# drive.net
KiCad netlist of a schematic drawn in Altium Designer
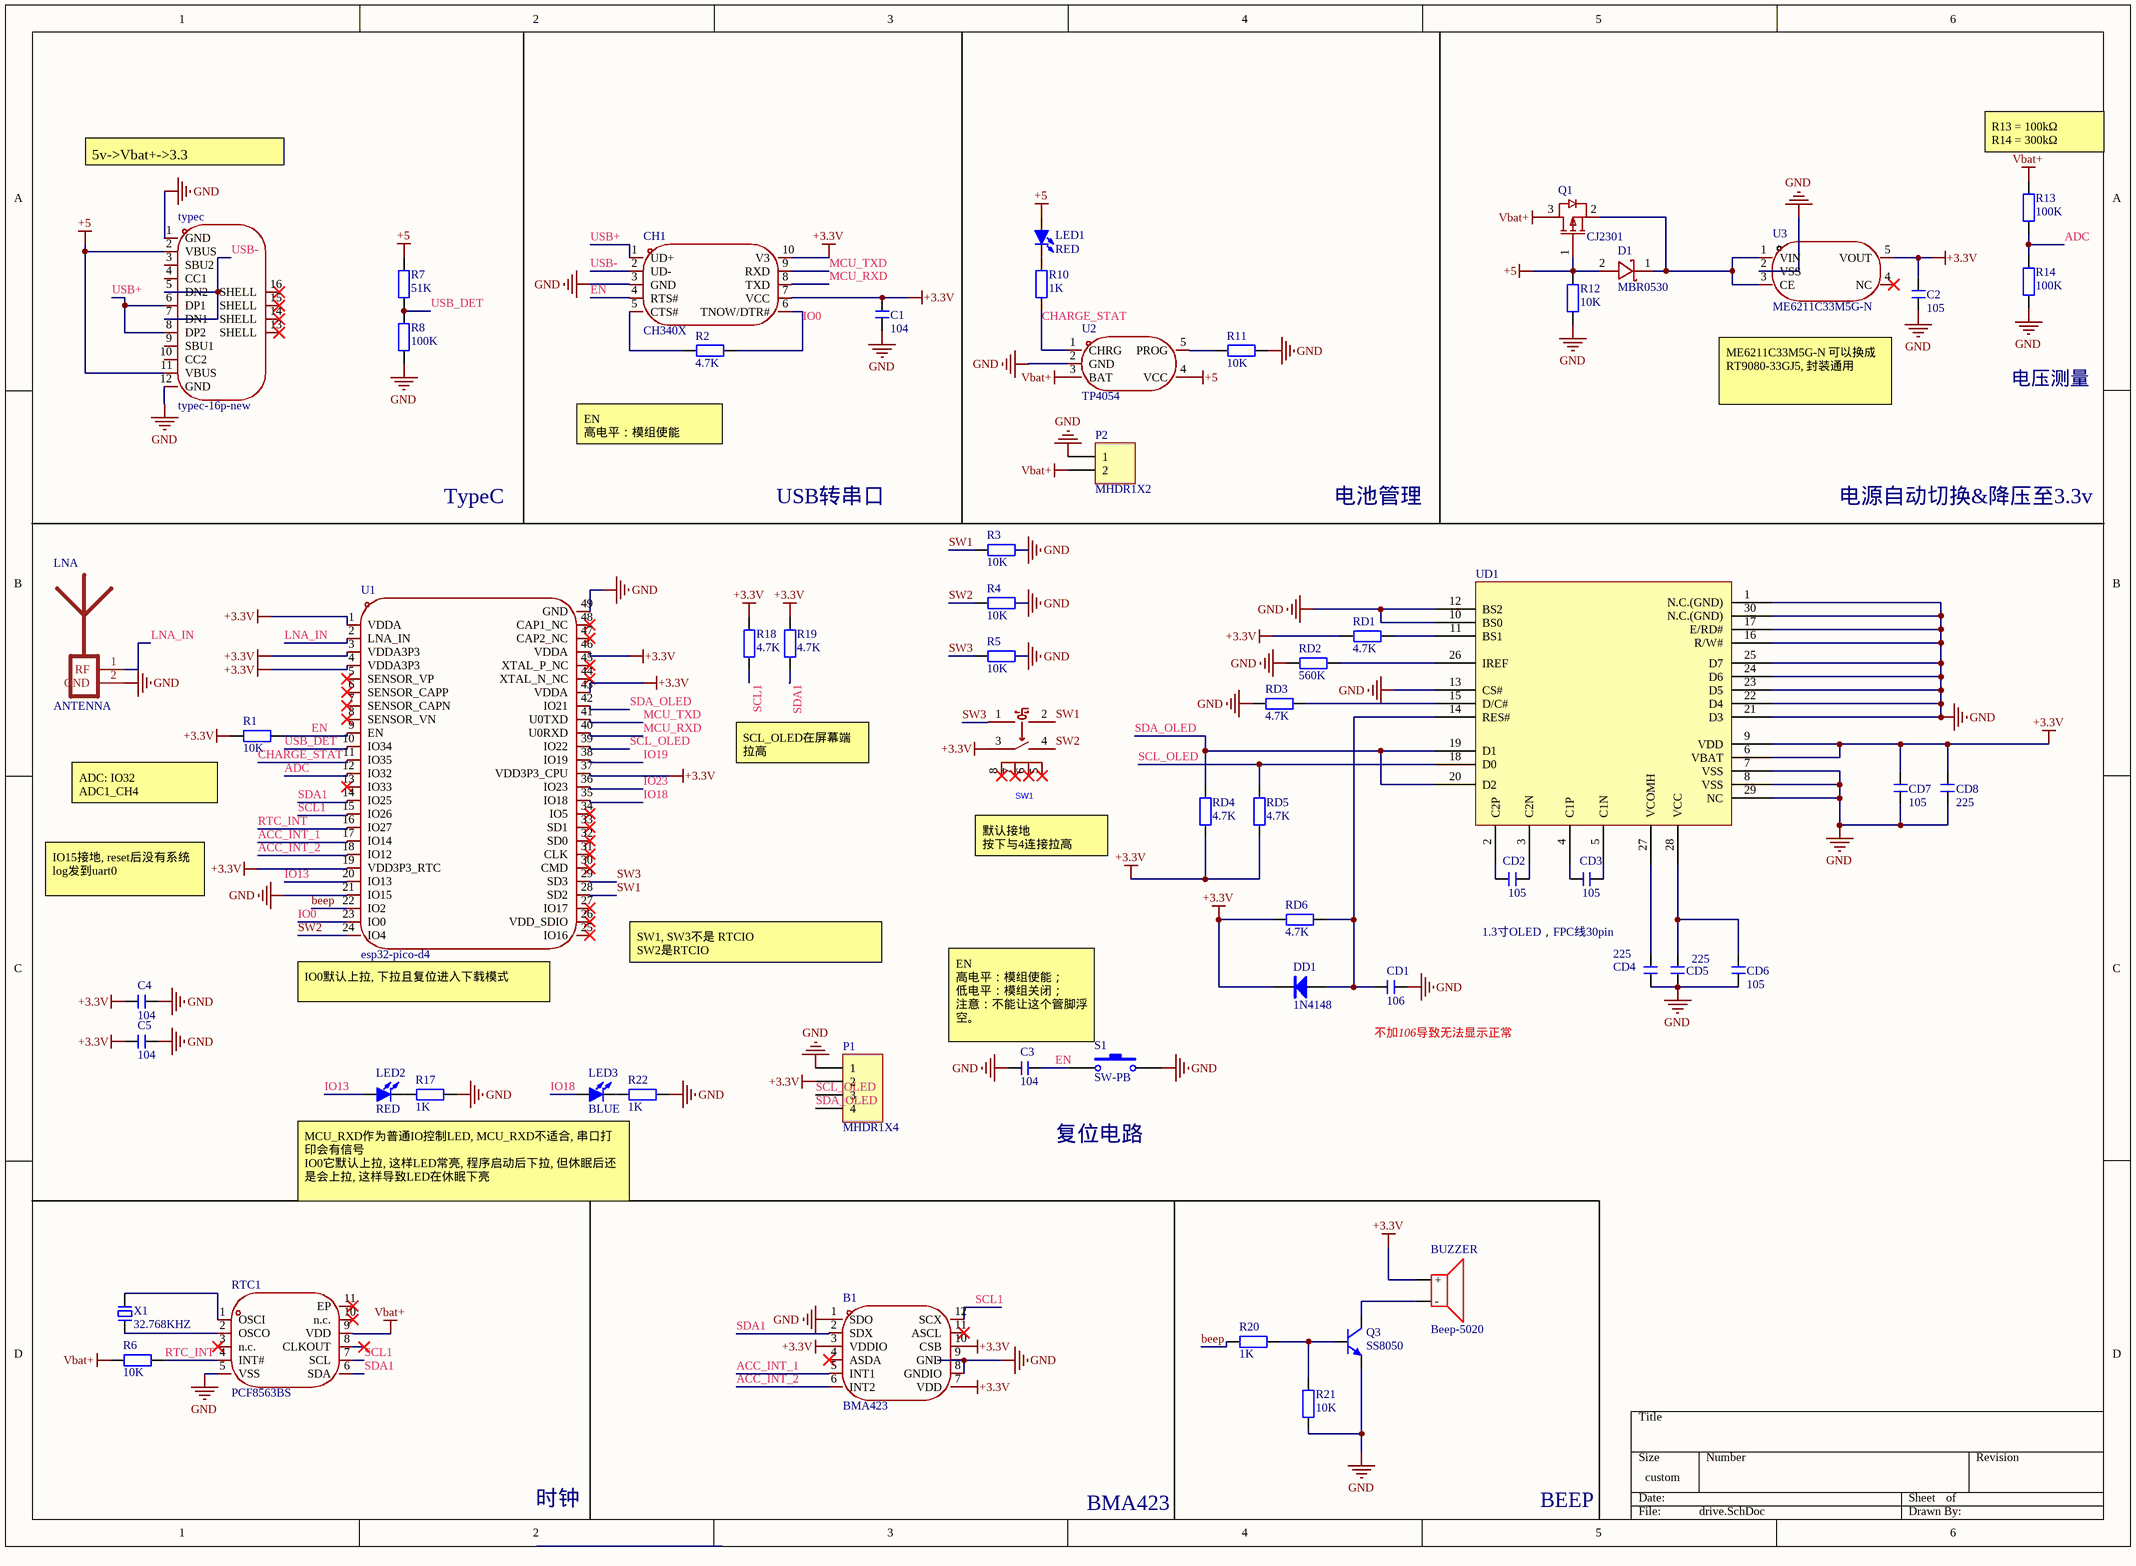
[diagram p0: drive.SchDoc]

(export (version "E")
  (design (tool "Eeschema 10.0.6"))
  (components
    (comp (ref "B1") (value "BMA423") (footprint "LGA-12(2x2)-2") (libsource (lib "Schlib1") (part "BMA423")))
    (comp (ref "BUZZER")
      (value "Beep-5020")
      (footprint "5020BUZZER")
      (description "贴片蜂鸣器5020最小封装")
      (libsource (lib "我的元件") (part "Beep-5020"))
    )
    (comp (ref "C1")
      (value "104")
      (footprint "C0402-min")
      (description "无极性贴片电容")
      (fields (field (name "版权归属") "源创客"))
      (libsource (lib "3.1   - 电阻-电容-电感") (part "C"))
    )
    (comp (ref "C2")
      (value "105")
      (footprint "C0402-min")
      (description "无极性贴片电容")
      (fields (field (name "版权归属") "源创客"))
      (libsource (lib "3.1   - 电阻-电容-电感") (part "C"))
    )
    (comp (ref "C3")
      (value "104")
      (footprint "C0402-min")
      (description "无极性贴片电容")
      (fields (field (name "版权归属") "源创客"))
      (libsource (lib "3.1   - 电阻-电容-电感") (part "C"))
    )
    (comp (ref "C4")
      (value "104")
      (footprint "C0402-min")
      (description "无极性贴片电容")
      (fields (field (name "版权归属") "源创客"))
      (libsource (lib "3.1   - 电阻-电容-电感") (part "C"))
    )
    (comp (ref "C5")
      (value "104")
      (footprint "C0402-min")
      (description "无极性贴片电容")
      (fields (field (name "版权归属") "源创客"))
      (libsource (lib "3.1   - 电阻-电容-电感") (part "C"))
    )
    (comp (ref "CD1")
      (value "106")
      (footprint "C0402-min")
      (description "无极性贴片电容")
      (fields (field (name "版权归属") "源创客"))
      (libsource (lib "3.1   - 电阻-电容-电感") (part "C"))
    )
    (comp (ref "CD2")
      (value "105")
      (footprint "C0402-min")
      (description "无极性贴片电容")
      (fields (field (name "版权归属") "源创客"))
      (libsource (lib "3.1   - 电阻-电容-电感") (part "C"))
    )
    (comp (ref "CD3")
      (value "105")
      (footprint "C0402-min")
      (description "无极性贴片电容")
      (fields (field (name "版权归属") "源创客"))
      (libsource (lib "3.1   - 电阻-电容-电感") (part "C"))
    )
    (comp (ref "CD4")
      (value "225")
      (footprint "C0402-min")
      (description "无极性贴片电容")
      (fields (field (name "版权归属") "源创客"))
      (libsource (lib "3.1   - 电阻-电容-电感") (part "C"))
    )
    (comp (ref "CD5")
      (value "225")
      (footprint "C0402-min")
      (description "无极性贴片电容")
      (fields (field (name "版权归属") "源创客"))
      (libsource (lib "3.1   - 电阻-电容-电感") (part "C"))
    )
    (comp (ref "CD6")
      (value "105")
      (footprint "C0402-min")
      (description "无极性贴片电容")
      (fields (field (name "版权归属") "源创客"))
      (libsource (lib "3.1   - 电阻-电容-电感") (part "C"))
    )
    (comp (ref "CD7")
      (value "105")
      (footprint "C0402-min")
      (description "无极性贴片电容")
      (fields (field (name "版权归属") "源创客"))
      (libsource (lib "3.1   - 电阻-电容-电感") (part "C"))
    )
    (comp (ref "CD8")
      (value "225")
      (footprint "C0402-min")
      (description "无极性贴片电容")
      (fields (field (name "版权归属") "源创客"))
      (libsource (lib "3.1   - 电阻-电容-电感") (part "C"))
    )
    (comp (ref "CH1") (value "CH340X") (footprint "MSOP-10") (libsource (lib "Schlib1") (part "CH340X")))
    (comp (ref "D1") (value "MBR0530") (footprint "SOD-123") (libsource (lib "Schlib1") (part "MBR0530T1G")))
    (comp (ref "DD1")
      (value "1N4148")
      (footprint "SOD-323")
      (description "高速开关二极管")
      (fields (field (name "版权归属") "源创客"))
      (libsource (lib "8.1   - 二极管-整流桥") (part "1N4148"))
    )
    (comp (ref "LED1")
      (value "RED")
      (footprint "LED0402")
      (description "贴片LED")
      (fields (field (name "版权归属") "源创客"))
      (libsource (lib "9.1   - LED") (part "LED-SMD"))
    )
    (comp (ref "LED2")
      (value "RED")
      (footprint "LED0402")
      (description "贴片LED")
      (fields (field (name "版权归属") "源创客"))
      (libsource (lib "9.1   - LED") (part "LED-SMD"))
    )
    (comp (ref "LED3")
      (value "BLUE")
      (footprint "LED0402")
      (description "贴片LED")
      (fields (field (name "版权归属") "源创客"))
      (libsource (lib "9.1   - LED") (part "LED-SMD"))
    )
    (comp (ref "LNA") (value "ANTENNA") (footprint "SWRA117D") (libsource (lib "Schlib1") (part "ANTENNA")))
    (comp (ref "P1")
      (value "MHDR1X4")
      (footprint "MHDR1X4")
      (description "Header, 4-Pin")
      (fields (field (name "PUBLISHER") "Altium Limited"))
      (libsource (lib "Miscellaneous Connectors") (part "MHDR1X4"))
    )
    (comp (ref "P2")
      (value "MHDR1X2")
      (footprint "MHDR1X2")
      (description "Header, 2-Pin")
      (fields (field (name "PUBLISHER") "Altium Limited"))
      (libsource (lib "Miscellaneous Connectors") (part "MHDR1X2"))
    )
    (comp (ref "Q1") (value "CJ2301") (footprint "SOT-23-3") (libsource (lib "Schlib1") (part "CJ2301")))
    (comp (ref "Q3")
      (value "SS8050")
      (footprint "SOT-23-3")
      (description "高频放大-NPN型")
      (fields (field (name "版权归属") "源创客"))
      (libsource (lib "6.2   - 三极管") (part "8050-SMD"))
    )
    (comp (ref "R1")
      (value "10K")
      (footprint "R0402")
      (description "贴片电阻")
      (fields (field (name "版权归属") "源创客"))
      (libsource (lib "3.1   - 电阻-电容-电感") (part "R"))
    )
    (comp (ref "R2")
      (value "4.7K")
      (footprint "R0402")
      (description "贴片电阻")
      (fields (field (name "版权归属") "源创客"))
      (libsource (lib "3.1   - 电阻-电容-电感") (part "R"))
    )
    (comp (ref "R3")
      (value "10K")
      (footprint "R0402")
      (description "贴片电阻")
      (fields (field (name "版权归属") "源创客"))
      (libsource (lib "3.1   - 电阻-电容-电感") (part "R"))
    )
    (comp (ref "R4")
      (value "10K")
      (footprint "R0402")
      (description "贴片电阻")
      (fields (field (name "版权归属") "源创客"))
      (libsource (lib "3.1   - 电阻-电容-电感") (part "R"))
    )
    (comp (ref "R5")
      (value "10K")
      (footprint "R0402")
      (description "贴片电阻")
      (fields (field (name "版权归属") "源创客"))
      (libsource (lib "3.1   - 电阻-电容-电感") (part "R"))
    )
    (comp (ref "R6")
      (value "10K")
      (footprint "R0402")
      (description "贴片电阻")
      (fields (field (name "版权归属") "源创客"))
      (libsource (lib "3.1   - 电阻-电容-电感") (part "R"))
    )
    (comp (ref "R7")
      (value "51K")
      (footprint "R0402")
      (description "贴片电阻")
      (fields (field (name "版权归属") "源创客"))
      (libsource (lib "3.1   - 电阻-电容-电感") (part "R"))
    )
    (comp (ref "R8")
      (value "100K")
      (footprint "R0402")
      (description "贴片电阻")
      (fields (field (name "版权归属") "源创客"))
      (libsource (lib "3.1   - 电阻-电容-电感") (part "R"))
    )
    (comp (ref "R10")
      (value "1K")
      (footprint "R0402")
      (description "贴片电阻")
      (fields (field (name "版权归属") "源创客"))
      (libsource (lib "3.1   - 电阻-电容-电感") (part "R"))
    )
    (comp (ref "R11")
      (value "10K")
      (footprint "R0402")
      (description "贴片电阻")
      (fields (field (name "版权归属") "源创客"))
      (libsource (lib "3.1   - 电阻-电容-电感") (part "R"))
    )
    (comp (ref "R12")
      (value "10K")
      (footprint "R0402")
      (description "贴片电阻")
      (fields (field (name "版权归属") "源创客"))
      (libsource (lib "3.1   - 电阻-电容-电感") (part "R"))
    )
    (comp (ref "R13")
      (value "100K")
      (footprint "R0402")
      (description "贴片电阻")
      (fields (field (name "版权归属") "源创客"))
      (libsource (lib "3.1   - 电阻-电容-电感") (part "R"))
    )
    (comp (ref "R14")
      (value "100K")
      (footprint "R0402")
      (description "贴片电阻")
      (fields (field (name "版权归属") "源创客"))
      (libsource (lib "3.1   - 电阻-电容-电感") (part "R"))
    )
    (comp (ref "R17")
      (value "1K")
      (footprint "R0402")
      (description "贴片电阻")
      (fields (field (name "版权归属") "源创客"))
      (libsource (lib "3.1   - 电阻-电容-电感") (part "R"))
    )
    (comp (ref "R18")
      (value "4.7K")
      (footprint "R0402")
      (description "贴片电阻")
      (fields (field (name "版权归属") "源创客"))
      (libsource (lib "3.1   - 电阻-电容-电感") (part "R"))
    )
    (comp (ref "R19")
      (value "4.7K")
      (footprint "R0402")
      (description "贴片电阻")
      (fields (field (name "版权归属") "源创客"))
      (libsource (lib "3.1   - 电阻-电容-电感") (part "R"))
    )
    (comp (ref "R20")
      (value "1K")
      (footprint "R0402")
      (description "贴片电阻")
      (fields (field (name "版权归属") "源创客"))
      (libsource (lib "3.1   - 电阻-电容-电感") (part "R"))
    )
    (comp (ref "R21")
      (value "10K")
      (footprint "R0402")
      (description "贴片电阻")
      (fields (field (name "版权归属") "源创客"))
      (libsource (lib "3.1   - 电阻-电容-电感") (part "R"))
    )
    (comp (ref "R22")
      (value "1K")
      (footprint "R0402")
      (description "贴片电阻")
      (fields (field (name "版权归属") "源创客"))
      (libsource (lib "3.1   - 电阻-电容-电感") (part "R"))
    )
    (comp (ref "RD1")
      (value "4.7K")
      (footprint "R0402")
      (description "贴片电阻")
      (fields (field (name "版权归属") "源创客"))
      (libsource (lib "3.1   - 电阻-电容-电感") (part "R"))
    )
    (comp (ref "RD2")
      (value "560K")
      (footprint "R0402")
      (description "贴片电阻")
      (fields (field (name "版权归属") "源创客"))
      (libsource (lib "3.1   - 电阻-电容-电感") (part "R"))
    )
    (comp (ref "RD3")
      (value "4.7K")
      (footprint "R0402")
      (description "贴片电阻")
      (fields (field (name "版权归属") "源创客"))
      (libsource (lib "3.1   - 电阻-电容-电感") (part "R"))
    )
    (comp (ref "RD4")
      (value "4.7K")
      (footprint "R0402")
      (description "贴片电阻")
      (fields (field (name "版权归属") "源创客"))
      (libsource (lib "3.1   - 电阻-电容-电感") (part "R"))
    )
    (comp (ref "RD5")
      (value "4.7K")
      (footprint "R0402")
      (description "贴片电阻")
      (fields (field (name "版权归属") "源创客"))
      (libsource (lib "3.1   - 电阻-电容-电感") (part "R"))
    )
    (comp (ref "RD6")
      (value "4.7K")
      (footprint "R0402")
      (description "贴片电阻")
      (fields (field (name "版权归属") "源创客"))
      (libsource (lib "3.1   - 电阻-电容-电感") (part "R"))
    )
    (comp (ref "RTC1")
      (value "PCF8563BS")
      (footprint "HVSON-10-EP(3x3)")
      (libsource (lib "Schlib1") (part "PCF8563BS"))
    )
    (comp (ref "S1")
      (value "SW-PB")
      (footprint "switch-2x3")
      (description "Switch")
      (fields (field (name "PUBLISHER") "Altium Limited"))
      (libsource (lib "Miscellaneous Devices") (part "SW-PB"))
    )
    (comp (ref "SW1")
      (value "TM-2024A")
      (footprint "LUNBO-min-out")
      (fields (field (name "MANUFACTURER") "XKB Connection(中国星坤)"))
      (libsource (lib "drive") (part "lunbo-min"))
    )
    (comp (ref "typec")
      (value "typec-16p-new")
      (footprint "type-c-16p-new")
      (libsource (lib "Schlib1") (part "typec-16p-new"))
    )
    (comp (ref "U1")
      (value "esp32-pico-d4")
      (footprint "QFN-48-EP(7x7)")
      (libsource (lib "Schlib1") (part "esp32-pico-d4"))
    )
    (comp (ref "U2") (value "TP4054") (footprint "SOT-23-5") (libsource (lib "Schlib1") (part "TP4054")))
    (comp (ref "U3")
      (value "ME6211C33M5G-N")
      (footprint "SOT-23-5")
      (libsource (lib "Schlib1") (part "ME6211C33M5G-N"))
    )
    (comp (ref "UD1")
      (value "1.3寸OLED，FPC线30pin")
      (footprint "0.96OLED")
      (libsource (lib "我的元件") (part "1.3寸OLED，FPC线30pin"))
    )
    (comp (ref "X1")
      (value "32.768KHZ")
      (footprint "SMD3215-2P")
      (description "2脚无源脚晶振")
      (fields (field (name "版权归属") "源创客"))
      (libsource (lib "10.1 - 保险丝-晶振") (part "XTAL-2P"))
    )
  )
  (nets
    (net (code "1") (name "+3.3V") (class "Default")
      (node (ref "B1") (pin "10") (pinfunction "CSB_10") (pintype "passive"))
      (node (ref "B1") (pin "3") (pinfunction "VDDIO_3") (pintype "passive"))
      (node (ref "B1") (pin "7") (pinfunction "VDD_7") (pintype "passive"))
      (node (ref "BUZZER") (pin "1") (pinfunction "+_1") (pintype "passive"))
      (node (ref "C1") (pin "2") (pinfunction "2_2") (pintype "passive"))
      (node (ref "C2") (pin "2") (pinfunction "2_2") (pintype "passive"))
      (node (ref "C4") (pin "2") (pinfunction "2_2") (pintype "passive"))
      (node (ref "C5") (pin "2") (pinfunction "2_2") (pintype "passive"))
      (node (ref "CD7") (pin "2") (pinfunction "2_2") (pintype "passive"))
      (node (ref "CD8") (pin "2") (pinfunction "2_2") (pintype "passive"))
      (node (ref "CH1") (pin "10") (pinfunction "V3_10") (pintype "passive"))
      (node (ref "CH1") (pin "7") (pinfunction "VCC_7") (pintype "passive"))
      (node (ref "DD1") (pin "2") (pinfunction "K_2") (pintype "passive"))
      (node (ref "P1") (pin "2") (pinfunction "2_2") (pintype "passive"))
      (node (ref "R1") (pin "1") (pinfunction "1_1") (pintype "passive"))
      (node (ref "R18") (pin "2") (pinfunction "2_2") (pintype "passive"))
      (node (ref "R19") (pin "2") (pinfunction "2_2") (pintype "passive"))
      (node (ref "RD1") (pin "1") (pinfunction "1_1") (pintype "passive"))
      (node (ref "RD4") (pin "1") (pinfunction "1_1") (pintype "passive"))
      (node (ref "RD5") (pin "1") (pinfunction "1_1") (pintype "passive"))
      (node (ref "RD6") (pin "1") (pinfunction "1_1") (pintype "passive"))
      (node (ref "SW1") (pin "3") (pinfunction "3_3") (pintype "passive"))
      (node (ref "U1") (pin "1") (pinfunction "VDDA_1") (pintype "passive"))
      (node (ref "U1") (pin "19") (pinfunction "VDD3P3_RTC_19") (pintype "passive"))
      (node (ref "U1") (pin "3") (pinfunction "VDDA3P3_3") (pintype "passive"))
      (node (ref "U1") (pin "37") (pinfunction "VDD3P3_CPU_37") (pintype "passive"))
      (node (ref "U1") (pin "4") (pinfunction "VDDA3P3_4") (pintype "passive"))
      (node (ref "U1") (pin "43") (pinfunction "VDDA_43") (pintype "passive"))
      (node (ref "U1") (pin "46") (pinfunction "VDDA_46") (pintype "passive"))
      (node (ref "U3") (pin "5") (pinfunction "VOUT_5") (pintype "passive"))
      (node (ref "UD1") (pin "6") (pinfunction "VBAT_6") (pintype "passive"))
      (node (ref "UD1") (pin "9") (pinfunction "VDD_9") (pintype "passive"))
    )
    (net (code "2") (name "+5") (class "Default")
      (node (ref "D1") (pin "2") (pinfunction "A_2") (pintype "passive"))
      (node (ref "LED1") (pin "1") (pinfunction "A_1") (pintype "passive"))
      (node (ref "Q1") (pin "1") (pinfunction "G_1") (pintype "passive"))
      (node (ref "R12") (pin "2") (pinfunction "2_2") (pintype "passive"))
      (node (ref "R7") (pin "1") (pinfunction "1_1") (pintype "passive"))
      (node (ref "U2") (pin "4") (pinfunction "VCC_4") (pintype "passive"))
      (node (ref "typec") (pin "11") (pinfunction "VBUS_11") (pintype "passive"))
      (node (ref "typec") (pin "2") (pinfunction "VBUS_2") (pintype "passive"))
    )
    (net (code "3") (name "/ACC_INT_1") (class "Default")
      (node (ref "B1") (pin "5") (pinfunction "INT1_5") (pintype "passive"))
      (node (ref "U1") (pin "17") (pinfunction "IO14_17") (pintype "passive"))
    )
    (net (code "4") (name "/ACC_INT_2") (class "Default")
      (node (ref "B1") (pin "6") (pinfunction "INT2_6") (pintype "passive"))
      (node (ref "U1") (pin "18") (pinfunction "IO12_18") (pintype "passive"))
    )
    (net (code "5") (name "/ADC") (class "Default")
      (node (ref "R13") (pin "1") (pinfunction "1_1") (pintype "passive"))
      (node (ref "R14") (pin "2") (pinfunction "2_2") (pintype "passive"))
      (node (ref "U1") (pin "12") (pinfunction "IO32_12") (pintype "passive"))
    )
    (net (code "6") (name "/CHARGE_STAT") (class "Default")
      (node (ref "R10") (pin "2") (pinfunction "2_2") (pintype "passive"))
      (node (ref "U1") (pin "11") (pinfunction "IO35_11") (pintype "passive"))
      (node (ref "U2") (pin "1") (pinfunction "CHRG_1") (pintype "passive"))
    )
    (net (code "7") (name "/EN") (class "Default")
      (node (ref "C3") (pin "2") (pinfunction "2_2") (pintype "passive"))
      (node (ref "CH1") (pin "4") (pinfunction "RTS#_4") (pintype "passive"))
      (node (ref "R1") (pin "2") (pinfunction "2_2") (pintype "passive"))
      (node (ref "S1") (pin "1") (pinfunction "1_1") (pintype "passive"))
      (node (ref "U1") (pin "9") (pinfunction "EN_9") (pintype "passive"))
    )
    (net (code "8") (name "/IO0") (class "Default")
      (node (ref "CH1") (pin "6") (pinfunction "TNOW/DTR#_6") (pintype "passive"))
      (node (ref "R2") (pin "1") (pinfunction "1_1") (pintype "passive"))
      (node (ref "U1") (pin "23") (pinfunction "IO0_23") (pintype "passive"))
    )
    (net (code "9") (name "/IO13") (class "Default")
      (node (ref "LED2") (pin "1") (pinfunction "A_1") (pintype "passive"))
      (node (ref "U1") (pin "20") (pinfunction "IO13_20") (pintype "passive"))
    )
    (net (code "10") (name "/IO18") (class "Default")
      (node (ref "LED3") (pin "1") (pinfunction "A_1") (pintype "passive"))
      (node (ref "U1") (pin "35") (pinfunction "IO18_35") (pintype "passive"))
    )
    (net (code "11") (name "/IO19") (class "Default")
      (node (ref "U1") (pin "38") (pinfunction "IO19_38") (pintype "passive"))
    )
    (net (code "12") (name "/IO23") (class "Default")
      (node (ref "U1") (pin "36") (pinfunction "IO23_36") (pintype "passive"))
    )
    (net (code "13") (name "/LNA_IN") (class "Default")
      (node (ref "LNA") (pin "1") (pinfunction "RF_1") (pintype "passive"))
      (node (ref "U1") (pin "2") (pinfunction "LNA_IN_2") (pintype "passive"))
    )
    (net (code "14") (name "/MCU_RXD") (class "Default")
      (node (ref "CH1") (pin "8") (pinfunction "TXD_8") (pintype "passive"))
      (node (ref "U1") (pin "40") (pinfunction "U0RXD_40") (pintype "passive"))
    )
    (net (code "15") (name "/MCU_TXD") (class "Default")
      (node (ref "CH1") (pin "9") (pinfunction "RXD_9") (pintype "passive"))
      (node (ref "U1") (pin "41") (pinfunction "U0TXD_41") (pintype "passive"))
    )
    (net (code "16") (name "/RTC_INT") (class "Default")
      (node (ref "R6") (pin "2") (pinfunction "2_2") (pintype "passive"))
      (node (ref "RTC1") (pin "4") (pinfunction "INT#_4") (pintype "passive"))
      (node (ref "U1") (pin "16") (pinfunction "IO27_16") (pintype "passive"))
    )
    (net (code "17") (name "/SCL1") (class "Default")
      (node (ref "B1") (pin "12") (pinfunction "SCX_12") (pintype "passive"))
      (node (ref "R18") (pin "1") (pinfunction "1_1") (pintype "passive"))
      (node (ref "RTC1") (pin "7") (pinfunction "SCL_7") (pintype "passive"))
      (node (ref "U1") (pin "15") (pinfunction "IO26_15") (pintype "passive"))
    )
    (net (code "18") (name "/SCL_OLED") (class "Default")
      (node (ref "P1") (pin "3") (pinfunction "3_3") (pintype "passive"))
      (node (ref "RD5") (pin "2") (pinfunction "2_2") (pintype "passive"))
      (node (ref "U1") (pin "39") (pinfunction "IO22_39") (pintype "passive"))
      (node (ref "UD1") (pin "18") (pinfunction "D0_18") (pintype "passive"))
    )
    (net (code "19") (name "/SDA1") (class "Default")
      (node (ref "B1") (pin "2") (pinfunction "SDX_2") (pintype "passive"))
      (node (ref "R19") (pin "1") (pinfunction "1_1") (pintype "passive"))
      (node (ref "RTC1") (pin "6") (pinfunction "SDA_6") (pintype "passive"))
      (node (ref "U1") (pin "14") (pinfunction "IO25_14") (pintype "passive"))
    )
    (net (code "20") (name "/SDA_OLED") (class "Default")
      (node (ref "P1") (pin "4") (pinfunction "4_4") (pintype "passive"))
      (node (ref "RD4") (pin "2") (pinfunction "2_2") (pintype "passive"))
      (node (ref "U1") (pin "42") (pinfunction "IO21_42") (pintype "passive"))
      (node (ref "UD1") (pin "19") (pinfunction "D1_19") (pintype "passive"))
      (node (ref "UD1") (pin "20") (pinfunction "D2_20") (pintype "passive"))
    )
    (net (code "21") (name "/SW1") (class "Default")
      (node (ref "R3") (pin "1") (pinfunction "1_1") (pintype "passive"))
      (node (ref "SW1") (pin "2") (pinfunction "2_2") (pintype "passive"))
      (node (ref "U1") (pin "28") (pinfunction "SD2_28") (pintype "passive"))
    )
    (net (code "22") (name "/SW2") (class "Default")
      (node (ref "R4") (pin "1") (pinfunction "1_1") (pintype "passive"))
      (node (ref "SW1") (pin "4") (pinfunction "4_4") (pintype "passive"))
      (node (ref "U1") (pin "24") (pinfunction "IO4_24") (pintype "passive"))
    )
    (net (code "23") (name "/SW3") (class "Default")
      (node (ref "R5") (pin "1") (pinfunction "1_1") (pintype "passive"))
      (node (ref "SW1") (pin "1") (pinfunction "1_1") (pintype "passive"))
      (node (ref "U1") (pin "29") (pinfunction "SD3_29") (pintype "passive"))
    )
    (net (code "24") (name "/USB+") (class "Default")
      (node (ref "CH1") (pin "1") (pinfunction "UD+_1") (pintype "passive"))
      (node (ref "typec") (pin "6") (pinfunction "DP1_6") (pintype "passive"))
      (node (ref "typec") (pin "8") (pinfunction "DP2_8") (pintype "passive"))
    )
    (net (code "25") (name "/USB-") (class "Default")
      (node (ref "CH1") (pin "2") (pinfunction "UD-_2") (pintype "passive"))
      (node (ref "typec") (pin "5") (pinfunction "DN2_5") (pintype "passive"))
      (node (ref "typec") (pin "7") (pinfunction "DN1_7") (pintype "passive"))
    )
    (net (code "26") (name "/USB_DET") (class "Default")
      (node (ref "R7") (pin "2") (pinfunction "2_2") (pintype "passive"))
      (node (ref "R8") (pin "1") (pinfunction "1_1") (pintype "passive"))
      (node (ref "U1") (pin "10") (pinfunction "IO34_10") (pintype "passive"))
    )
    (net (code "27") (name "/beep") (class "Default")
      (node (ref "R20") (pin "1") (pinfunction "1_1") (pintype "passive"))
      (node (ref "U1") (pin "22") (pinfunction "IO2_22") (pintype "passive"))
    )
    (net (code "28") (name "GND") (class "Default")
      (node (ref "B1") (pin "1") (pinfunction "SDO_1") (pintype "passive"))
      (node (ref "B1") (pin "8") (pinfunction "GNDIO_8") (pintype "passive"))
      (node (ref "B1") (pin "9") (pinfunction "GND_9") (pintype "passive"))
      (node (ref "C1") (pin "1") (pinfunction "1_1") (pintype "passive"))
      (node (ref "C2") (pin "1") (pinfunction "1_1") (pintype "passive"))
      (node (ref "C3") (pin "1") (pinfunction "1_1") (pintype "passive"))
      (node (ref "C4") (pin "1") (pinfunction "1_1") (pintype "passive"))
      (node (ref "C5") (pin "1") (pinfunction "1_1") (pintype "passive"))
      (node (ref "CD1") (pin "2") (pinfunction "2_2") (pintype "passive"))
      (node (ref "CD4") (pin "1") (pinfunction "1_1") (pintype "passive"))
      (node (ref "CD5") (pin "1") (pinfunction "1_1") (pintype "passive"))
      (node (ref "CD6") (pin "1") (pinfunction "1_1") (pintype "passive"))
      (node (ref "CD7") (pin "1") (pinfunction "1_1") (pintype "passive"))
      (node (ref "CD8") (pin "1") (pinfunction "1_1") (pintype "passive"))
      (node (ref "CH1") (pin "3") (pinfunction "GND_3") (pintype "passive"))
      (node (ref "LNA") (pin "2") (pinfunction "GND_2") (pintype "passive"))
      (node (ref "P1") (pin "1") (pinfunction "1_1") (pintype "passive"))
      (node (ref "P2") (pin "1") (pinfunction "1_1") (pintype "passive"))
      (node (ref "Q3") (pin "2") (pinfunction "E_2") (pintype "passive"))
      (node (ref "R11") (pin "1") (pinfunction "1_1") (pintype "passive"))
      (node (ref "R12") (pin "1") (pinfunction "1_1") (pintype "passive"))
      (node (ref "R14") (pin "1") (pinfunction "1_1") (pintype "passive"))
      (node (ref "R17") (pin "2") (pinfunction "2_2") (pintype "passive"))
      (node (ref "R21") (pin "1") (pinfunction "1_1") (pintype "passive"))
      (node (ref "R22") (pin "2") (pinfunction "2_2") (pintype "passive"))
      (node (ref "R3") (pin "2") (pinfunction "2_2") (pintype "passive"))
      (node (ref "R4") (pin "2") (pinfunction "2_2") (pintype "passive"))
      (node (ref "R5") (pin "2") (pinfunction "2_2") (pintype "passive"))
      (node (ref "R8") (pin "2") (pinfunction "2_2") (pintype "passive"))
      (node (ref "RD2") (pin "1") (pinfunction "1_1") (pintype "passive"))
      (node (ref "RD3") (pin "2") (pinfunction "2_2") (pintype "passive"))
      (node (ref "RTC1") (pin "5") (pinfunction "VSS_5") (pintype "passive"))
      (node (ref "S1") (pin "2") (pinfunction "2_2") (pintype "passive"))
      (node (ref "U1") (pin "21") (pinfunction "IO15_21") (pintype "passive"))
      (node (ref "U1") (pin "49") (pinfunction "GND_49") (pintype "passive"))
      (node (ref "U2") (pin "2") (pinfunction "GND_2") (pintype "passive"))
      (node (ref "U3") (pin "2") (pinfunction "VSS_2") (pintype "passive"))
      (node (ref "UD1") (pin "1") (pinfunction "N.C.(GND)_1") (pintype "passive"))
      (node (ref "UD1") (pin "10") (pinfunction "BS0_10") (pintype "passive"))
      (node (ref "UD1") (pin "12") (pinfunction "BS2_12") (pintype "passive"))
      (node (ref "UD1") (pin "13") (pinfunction "CS#_13") (pintype "passive"))
      (node (ref "UD1") (pin "16") (pinfunction "R/W#_16") (pintype "passive"))
      (node (ref "UD1") (pin "17") (pinfunction "E/RD#_17") (pintype "passive"))
      (node (ref "UD1") (pin "21") (pinfunction "D3_21") (pintype "passive"))
      (node (ref "UD1") (pin "22") (pinfunction "D4_22") (pintype "passive"))
      (node (ref "UD1") (pin "23") (pinfunction "D5_23") (pintype "passive"))
      (node (ref "UD1") (pin "24") (pinfunction "D6_24") (pintype "passive"))
      (node (ref "UD1") (pin "25") (pinfunction "D7_25") (pintype "passive"))
      (node (ref "UD1") (pin "29") (pinfunction "NC_29") (pintype "passive"))
      (node (ref "UD1") (pin "30") (pinfunction "N.C.(GND)_30") (pintype "passive"))
      (node (ref "UD1") (pin "7") (pinfunction "VSS_7") (pintype "passive"))
      (node (ref "UD1") (pin "8") (pinfunction "VSS_8") (pintype "passive"))
      (node (ref "typec") (pin "1") (pinfunction "GND_1") (pintype "passive"))
      (node (ref "typec") (pin "12") (pinfunction "GND_12") (pintype "passive"))
    )
    (net (code "29") (name "Net-(BUZZER--)") (class "Default")
      (node (ref "BUZZER") (pin "2") (pinfunction "-_2") (pintype "passive"))
      (node (ref "Q3") (pin "3") (pinfunction "C_3") (pintype "passive"))
    )
    (net (code "30") (name "Net-(CH1-CTS#)") (class "Default")
      (node (ref "CH1") (pin "5") (pinfunction "CTS#_5") (pintype "passive"))
      (node (ref "R2") (pin "2") (pinfunction "2_2") (pintype "passive"))
    )
    (net (code "31") (name "Net-(D1-C)") (class "Default")
      (node (ref "D1") (pin "1") (pinfunction "C_1") (pintype "passive"))
      (node (ref "Q1") (pin "2") (pinfunction "S_2") (pintype "passive"))
      (node (ref "U3") (pin "1") (pinfunction "VIN_1") (pintype "passive"))
      (node (ref "U3") (pin "3") (pinfunction "CE_3") (pintype "passive"))
    )
    (net (code "32") (name "Net-(DD1-A)") (class "Default")
      (node (ref "CD1") (pin "1") (pinfunction "1_1") (pintype "passive"))
      (node (ref "DD1") (pin "1") (pinfunction "A_1") (pintype "passive"))
      (node (ref "RD6") (pin "2") (pinfunction "2_2") (pintype "passive"))
      (node (ref "UD1") (pin "14") (pinfunction "RES#_14") (pintype "passive"))
    )
    (net (code "33") (name "Net-(LED1-K)") (class "Default")
      (node (ref "LED1") (pin "2") (pinfunction "K_2") (pintype "passive"))
      (node (ref "R10") (pin "1") (pinfunction "1_1") (pintype "passive"))
    )
    (net (code "34") (name "Net-(LED2-K)") (class "Default")
      (node (ref "LED2") (pin "2") (pinfunction "K_2") (pintype "passive"))
      (node (ref "R17") (pin "1") (pinfunction "1_1") (pintype "passive"))
    )
    (net (code "35") (name "Net-(LED3-K)") (class "Default")
      (node (ref "LED3") (pin "2") (pinfunction "K_2") (pintype "passive"))
      (node (ref "R22") (pin "1") (pinfunction "1_1") (pintype "passive"))
    )
    (net (code "36") (name "Net-(Q3-B)") (class "Default")
      (node (ref "Q3") (pin "1") (pinfunction "B_1") (pintype "passive"))
      (node (ref "R20") (pin "2") (pinfunction "2_2") (pintype "passive"))
      (node (ref "R21") (pin "2") (pinfunction "2_2") (pintype "passive"))
    )
    (net (code "37") (name "Net-(RTC1-OSCI)") (class "Default")
      (node (ref "RTC1") (pin "1") (pinfunction "OSCI_1") (pintype "passive"))
      (node (ref "X1") (pin "2") (pinfunction "2_2") (pintype "passive"))
    )
    (net (code "38") (name "Net-(RTC1-OSCO)") (class "Default")
      (node (ref "RTC1") (pin "2") (pinfunction "OSCO_2") (pintype "passive"))
      (node (ref "X1") (pin "1") (pinfunction "1_1") (pintype "passive"))
    )
    (net (code "39") (name "Net-(U2-PROG)") (class "Default")
      (node (ref "R11") (pin "2") (pinfunction "2_2") (pintype "passive"))
      (node (ref "U2") (pin "5") (pinfunction "PROG_5") (pintype "passive"))
    )
    (net (code "40") (name "Net-(UD1-BS1)") (class "Default")
      (node (ref "RD1") (pin "2") (pinfunction "2_2") (pintype "passive"))
      (node (ref "UD1") (pin "11") (pinfunction "BS1_11") (pintype "passive"))
    )
    (net (code "41") (name "Net-(UD1-C1N)") (class "Default")
      (node (ref "CD3") (pin "2") (pinfunction "2_2") (pintype "passive"))
      (node (ref "UD1") (pin "5") (pinfunction "C1N_5") (pintype "passive"))
    )
    (net (code "42") (name "Net-(UD1-C1P)") (class "Default")
      (node (ref "CD3") (pin "1") (pinfunction "1_1") (pintype "passive"))
      (node (ref "UD1") (pin "4") (pinfunction "C1P_4") (pintype "passive"))
    )
    (net (code "43") (name "Net-(UD1-C2N)") (class "Default")
      (node (ref "CD2") (pin "2") (pinfunction "2_2") (pintype "passive"))
      (node (ref "UD1") (pin "3") (pinfunction "C2N_3") (pintype "passive"))
    )
    (net (code "44") (name "Net-(UD1-C2P)") (class "Default")
      (node (ref "CD2") (pin "1") (pinfunction "1_1") (pintype "passive"))
      (node (ref "UD1") (pin "2") (pinfunction "C2P_2") (pintype "passive"))
    )
    (net (code "45") (name "Net-(UD1-D{slash}C#)") (class "Default")
      (node (ref "RD3") (pin "1") (pinfunction "1_1") (pintype "passive"))
      (node (ref "UD1") (pin "15") (pinfunction "D/C#_15") (pintype "passive"))
    )
    (net (code "46") (name "Net-(UD1-IREF)") (class "Default")
      (node (ref "RD2") (pin "2") (pinfunction "2_2") (pintype "passive"))
      (node (ref "UD1") (pin "26") (pinfunction "IREF_26") (pintype "passive"))
    )
    (net (code "47") (name "Net-(UD1-VCC)") (class "Default")
      (node (ref "CD5") (pin "2") (pinfunction "2_2") (pintype "passive"))
      (node (ref "CD6") (pin "2") (pinfunction "2_2") (pintype "passive"))
      (node (ref "UD1") (pin "28") (pinfunction "VCC_28") (pintype "passive"))
    )
    (net (code "48") (name "Net-(UD1-VCOMH)") (class "Default")
      (node (ref "CD4") (pin "2") (pinfunction "2_2") (pintype "passive"))
      (node (ref "UD1") (pin "27") (pinfunction "VCOMH_27") (pintype "passive"))
    )
    (net (code "49") (name "Vbat+") (class "Default")
      (node (ref "P2") (pin "2") (pinfunction "2_2") (pintype "passive"))
      (node (ref "Q1") (pin "3") (pinfunction "D_3") (pintype "passive"))
      (node (ref "R13") (pin "2") (pinfunction "2_2") (pintype "passive"))
      (node (ref "R6") (pin "1") (pinfunction "1_1") (pintype "passive"))
      (node (ref "RTC1") (pin "9") (pinfunction "VDD_9") (pintype "passive"))
      (node (ref "U2") (pin "3") (pinfunction "BAT_3") (pintype "passive"))
    )
    (net (code "50") (name "unconnected-(B1-ASCL-Pad11)") (class "Default")
      (node (ref "B1") (pin "11") (pinfunction "ASCL_11") (pintype "passive+no_connect"))
    )
    (net (code "51") (name "unconnected-(B1-ASDA-Pad4)") (class "Default")
      (node (ref "B1") (pin "4") (pinfunction "ASDA_4") (pintype "passive+no_connect"))
    )
    (net (code "52") (name "unconnected-(RTC1-CLKOUT-Pad8)") (class "Default")
      (node (ref "RTC1") (pin "8") (pinfunction "CLKOUT_8") (pintype "passive+no_connect"))
    )
    (net (code "53") (name "unconnected-(RTC1-EP-Pad11)") (class "Default")
      (node (ref "RTC1") (pin "11") (pinfunction "EP_11") (pintype "passive+no_connect"))
    )
    (net (code "54") (name "unconnected-(RTC1-n.c.-Pad3)") (class "Default")
      (node (ref "RTC1") (pin "3") (pinfunction "n.c._3") (pintype "passive+no_connect"))
    )
    (net (code "55") (name "unconnected-(RTC1-n.c.-Pad10)") (class "Default")
      (node (ref "RTC1") (pin "10") (pinfunction "n.c._10") (pintype "passive+no_connect"))
    )
    (net (code "56") (name "unconnected-(SW1-Pad5)") (class "Default")
      (node (ref "SW1") (pin "5") (pinfunction "5_5") (pintype "passive+no_connect"))
    )
    (net (code "57") (name "unconnected-(SW1-Pad6)") (class "Default")
      (node (ref "SW1") (pin "6") (pinfunction "6_6") (pintype "passive+no_connect"))
    )
    (net (code "58") (name "unconnected-(SW1-Pad7)") (class "Default")
      (node (ref "SW1") (pin "7") (pinfunction "7_7") (pintype "passive+no_connect"))
    )
    (net (code "59") (name "unconnected-(SW1-Pad8)") (class "Default")
      (node (ref "SW1") (pin "8") (pinfunction "8_8") (pintype "passive+no_connect"))
    )
    (net (code "60") (name "unconnected-(U1-CAP1_NC-Pad48)") (class "Default")
      (node (ref "U1") (pin "48") (pinfunction "CAP1_NC_48") (pintype "passive+no_connect"))
    )
    (net (code "61") (name "unconnected-(U1-CAP2_NC-Pad47)") (class "Default")
      (node (ref "U1") (pin "47") (pinfunction "CAP2_NC_47") (pintype "passive+no_connect"))
    )
    (net (code "62") (name "unconnected-(U1-CLK-Pad31)") (class "Default")
      (node (ref "U1") (pin "31") (pinfunction "CLK_31") (pintype "passive+no_connect"))
    )
    (net (code "63") (name "unconnected-(U1-CMD-Pad30)") (class "Default")
      (node (ref "U1") (pin "30") (pinfunction "CMD_30") (pintype "passive"))
    )
    (net (code "64") (name "unconnected-(U1-IO5-Pad34)") (class "Default")
      (node (ref "U1") (pin "34") (pinfunction "IO5_34") (pintype "passive+no_connect"))
    )
    (net (code "65") (name "unconnected-(U1-IO16-Pad25)") (class "Default")
      (node (ref "U1") (pin "25") (pinfunction "IO16_25") (pintype "passive+no_connect"))
    )
    (net (code "66") (name "unconnected-(U1-IO17-Pad27)") (class "Default")
      (node (ref "U1") (pin "27") (pinfunction "IO17_27") (pintype "passive+no_connect"))
    )
    (net (code "67") (name "unconnected-(U1-IO33-Pad13)") (class "Default")
      (node (ref "U1") (pin "13") (pinfunction "IO33_13") (pintype "passive+no_connect"))
    )
    (net (code "68") (name "unconnected-(U1-SD0-Pad32)") (class "Default")
      (node (ref "U1") (pin "32") (pinfunction "SD0_32") (pintype "passive+no_connect"))
    )
    (net (code "69") (name "unconnected-(U1-SD1-Pad33)") (class "Default")
      (node (ref "U1") (pin "33") (pinfunction "SD1_33") (pintype "passive+no_connect"))
    )
    (net (code "70") (name "unconnected-(U1-SENSOR_CAPN-Pad7)") (class "Default")
      (node (ref "U1") (pin "7") (pinfunction "SENSOR_CAPN_7") (pintype "passive+no_connect"))
    )
    (net (code "71") (name "unconnected-(U1-SENSOR_CAPP-Pad6)") (class "Default")
      (node (ref "U1") (pin "6") (pinfunction "SENSOR_CAPP_6") (pintype "passive+no_connect"))
    )
    (net (code "72") (name "unconnected-(U1-SENSOR_VN-Pad8)") (class "Default")
      (node (ref "U1") (pin "8") (pinfunction "SENSOR_VN_8") (pintype "passive+no_connect"))
    )
    (net (code "73") (name "unconnected-(U1-SENSOR_VP-Pad5)") (class "Default")
      (node (ref "U1") (pin "5") (pinfunction "SENSOR_VP_5") (pintype "passive+no_connect"))
    )
    (net (code "74") (name "unconnected-(U1-VDD_SDIO-Pad26)") (class "Default")
      (node (ref "U1") (pin "26") (pinfunction "VDD_SDIO_26") (pintype "passive+no_connect"))
    )
    (net (code "75") (name "unconnected-(U1-XTAL_N_NC-Pad44)") (class "Default")
      (node (ref "U1") (pin "44") (pinfunction "XTAL_N_NC_44") (pintype "passive+no_connect"))
    )
    (net (code "76") (name "unconnected-(U1-XTAL_P_NC-Pad45)") (class "Default")
      (node (ref "U1") (pin "45") (pinfunction "XTAL_P_NC_45") (pintype "passive+no_connect"))
    )
    (net (code "77") (name "unconnected-(U3-NC-Pad4)") (class "Default")
      (node (ref "U3") (pin "4") (pinfunction "NC_4") (pintype "passive+no_connect"))
    )
    (net (code "78") (name "unconnected-(typec-CC1-Pad4)") (class "Default")
      (node (ref "typec") (pin "4") (pinfunction "CC1_4") (pintype "passive"))
    )
    (net (code "79") (name "unconnected-(typec-CC2-Pad10)") (class "Default")
      (node (ref "typec") (pin "10") (pinfunction "CC2_10") (pintype "passive"))
    )
    (net (code "80") (name "unconnected-(typec-SBU1-Pad9)") (class "Default")
      (node (ref "typec") (pin "9") (pinfunction "SBU1_9") (pintype "passive"))
    )
    (net (code "81") (name "unconnected-(typec-SBU2-Pad3)") (class "Default")
      (node (ref "typec") (pin "3") (pinfunction "SBU2_3") (pintype "passive"))
    )
    (net (code "82") (name "unconnected-(typec-SHELL-Pad13)") (class "Default")
      (node (ref "typec") (pin "13") (pinfunction "SHELL_13") (pintype "passive+no_connect"))
    )
    (net (code "83") (name "unconnected-(typec-SHELL-Pad14)") (class "Default")
      (node (ref "typec") (pin "14") (pinfunction "SHELL_14") (pintype "passive+no_connect"))
    )
    (net (code "84") (name "unconnected-(typec-SHELL-Pad15)") (class "Default")
      (node (ref "typec") (pin "15") (pinfunction "SHELL_15") (pintype "passive+no_connect"))
    )
    (net (code "85") (name "unconnected-(typec-SHELL-Pad16)") (class "Default")
      (node (ref "typec") (pin "16") (pinfunction "SHELL_16") (pintype "passive+no_connect"))
    )
  )
)
